# SignalEditor.net
KiCad netlist of a schematic drawn in EAGLE
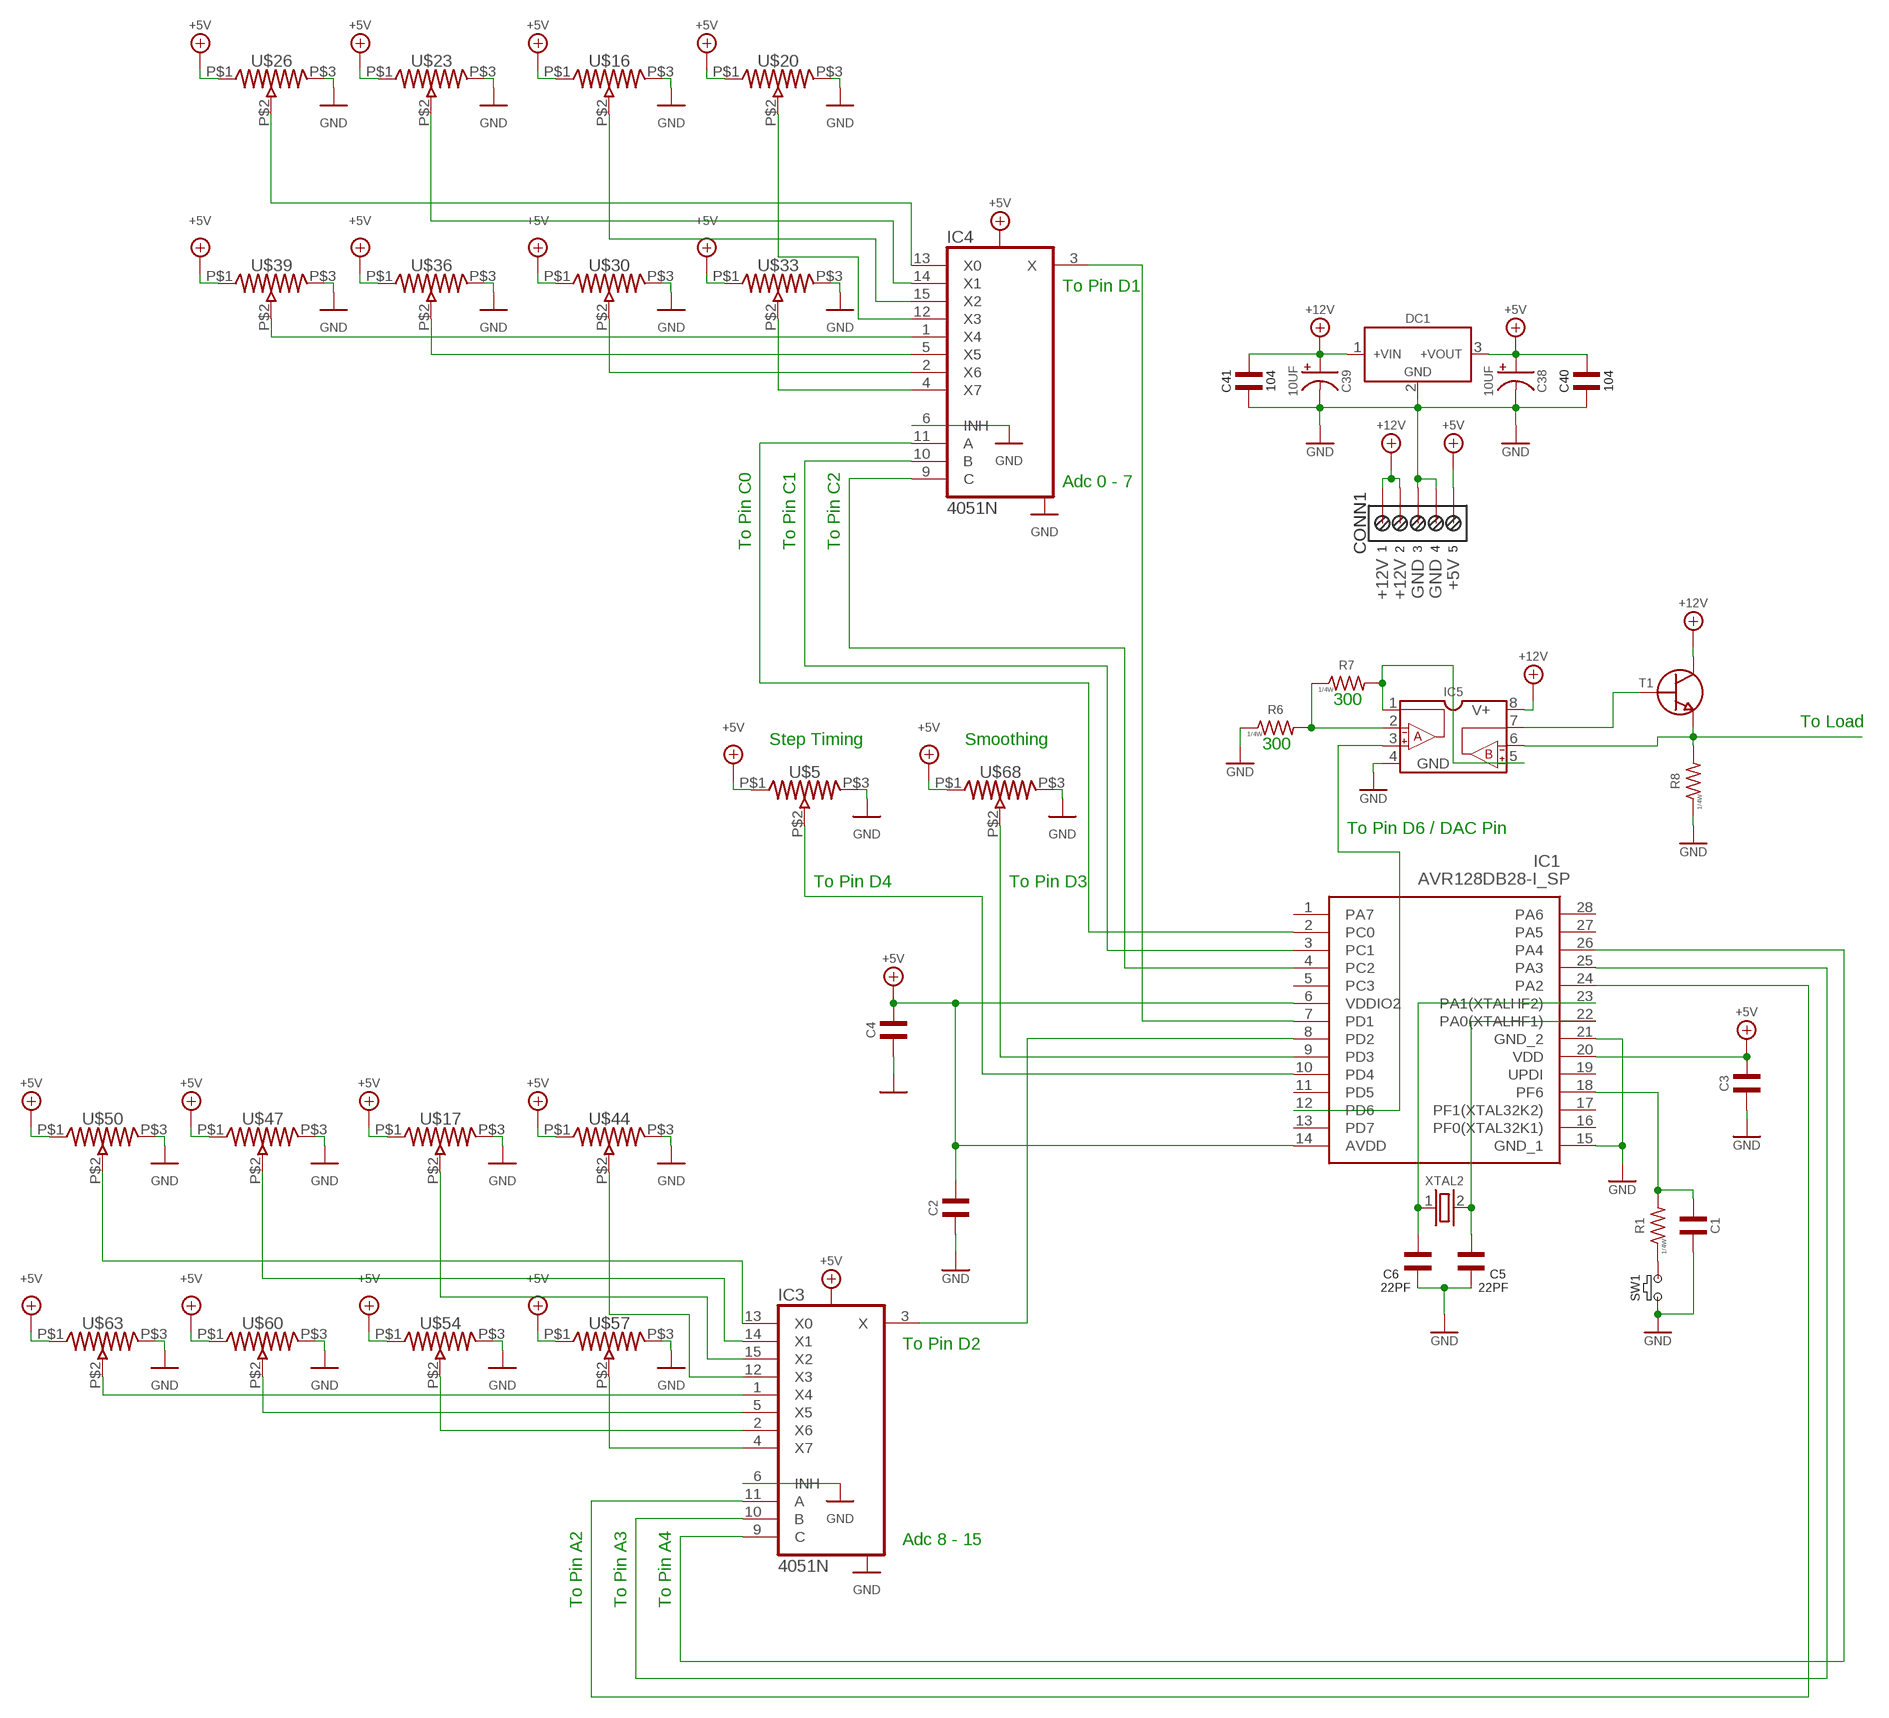
[diagram p0: schematic, sheet 1]

(export (version "E")
  (design (tool "Eeschema 10.0.6"))
  (components
    (comp (ref "C1")
      (value "040-005-032")
      (footprint "eagle-import:CAPACITOR-CERAMIC-AXIAL")
      (libsource (lib "eagle-import") (part "040-005-032"))
    )
    (comp (ref "C2")
      (value "040-005-032")
      (footprint "eagle-import:CAPACITOR-CERAMIC-AXIAL")
      (libsource (lib "eagle-import") (part "040-005-032"))
    )
    (comp (ref "C3")
      (value "040-005-032")
      (footprint "eagle-import:CAPACITOR-CERAMIC-AXIAL")
      (libsource (lib "eagle-import") (part "040-005-032"))
    )
    (comp (ref "C4")
      (value "040-005-032")
      (footprint "eagle-import:CAPACITOR-CERAMIC-AXIAL")
      (libsource (lib "eagle-import") (part "040-005-032"))
    )
    (comp (ref "C5")
      (value "22PF")
      (footprint "eagle-import:CAPACITOR-CERAMIC-AXIAL")
      (libsource (lib "eagle-import") (part "040-005-038"))
    )
    (comp (ref "C6")
      (value "22PF")
      (footprint "eagle-import:CAPACITOR-CERAMIC-AXIAL")
      (libsource (lib "eagle-import") (part "040-005-038"))
    )
    (comp (ref "C38")
      (value "10UF")
      (footprint "eagle-import:CAPACITOR-RADIAL")
      (libsource (lib "eagle-import") (part "040-005-005"))
    )
    (comp (ref "C39")
      (value "10UF")
      (footprint "eagle-import:CAPACITOR-RADIAL")
      (libsource (lib "eagle-import") (part "040-005-005"))
    )
    (comp (ref "C40")
      (value "104")
      (footprint "eagle-import:CAPACITOR-CERAMIC-AXIAL")
      (libsource (lib "eagle-import") (part "040-005-032"))
    )
    (comp (ref "C41")
      (value "104")
      (footprint "eagle-import:CAPACITOR-CERAMIC-AXIAL")
      (libsource (lib "eagle-import") (part "040-005-032"))
    )
    (comp (ref "CONN1")
      (value "030-019-017")
      (footprint "eagle-import:030-007-024")
      (libsource (lib "eagle-import") (part "030-019-017"))
    )
    (comp (ref "DC1")
      (value "5V-DC-DC-CONVERTER_RECOM")
      (footprint "eagle-import:5V-DC-DC-CONVERTER_RECOM")
      (libsource (lib "eagle-import") (part "5V-DC-DC-CONVERTER_RECOM"))
    )
    (comp (ref "IC1")
      (value "AVR128DB28-I_SP")
      (footprint "eagle-import:DIP794W56P254L3486H508Q28N")
      (fields
        (field (name "MANUFACTURER_PART_NUMBER") "AVR128DB28-I/SP")
        (field (name "MOUSER_PART_NUMBER") "579-AVR128DB28-I/SP")
      )
      (libsource (lib "eagle-import") (part "AVR128DB28-I_SP"))
    )
    (comp (ref "IC3")
      (value "4051N")
      (footprint "eagle-import:DIL16")
      (libsource (lib "eagle-import") (part "4051N"))
    )
    (comp (ref "IC4")
      (value "4051N")
      (footprint "eagle-import:DIL16")
      (libsource (lib "eagle-import") (part "4051N"))
    )
    (comp (ref "IC5")
      (value "040-002-002")
      (footprint "eagle-import:040-010-001")
      (libsource (lib "eagle-import") (part "040-002-002"))
    )
    (comp (ref "R1")
      (value "040-001-024")
      (footprint "eagle-import:RESISTOR-1_4W")
      (libsource (lib "eagle-import") (part "040-001-024"))
    )
    (comp (ref "R6")
      (value "040-001-017")
      (footprint "eagle-import:RESISTOR-1_4W")
      (libsource (lib "eagle-import") (part "040-001-017"))
    )
    (comp (ref "R7")
      (value "040-001-017")
      (footprint "eagle-import:RESISTOR-1_4W")
      (libsource (lib "eagle-import") (part "040-001-017"))
    )
    (comp (ref "R8")
      (value "040-001-015")
      (footprint "eagle-import:RESISTOR-1_4W")
      (libsource (lib "eagle-import") (part "040-001-015"))
    )
    (comp (ref "SW1")
      (value "030-011-050")
      (footprint "eagle-import:SWITCH-PB-SMD")
      (libsource (lib "eagle-import") (part "030-011-050"))
    )
    (comp (ref "T1")
      (value "040-004-002")
      (footprint "eagle-import:TRANSISTOR-TO92")
      (libsource (lib "eagle-import") (part "040-004-002"))
    )
    (comp (ref "U$5")
      (value "5K_POT_THROUGH_HOLE")
      (footprint "eagle-import:POT-TRIM-SMALL")
      (libsource (lib "eagle-import") (part "5K_POT_THROUGH_HOLE"))
    )
    (comp (ref "U$16")
      (value "5K_POT_THROUGH_HOLE")
      (footprint "eagle-import:POT-TRIM-SMALL")
      (libsource (lib "eagle-import") (part "5K_POT_THROUGH_HOLE"))
    )
    (comp (ref "U$17")
      (value "5K_POT_THROUGH_HOLE")
      (footprint "eagle-import:POT-TRIM-SMALL")
      (libsource (lib "eagle-import") (part "5K_POT_THROUGH_HOLE"))
    )
    (comp (ref "U$20")
      (value "5K_POT_THROUGH_HOLE")
      (footprint "eagle-import:POT-TRIM-SMALL")
      (libsource (lib "eagle-import") (part "5K_POT_THROUGH_HOLE"))
    )
    (comp (ref "U$23")
      (value "5K_POT_THROUGH_HOLE")
      (footprint "eagle-import:POT-TRIM-SMALL")
      (libsource (lib "eagle-import") (part "5K_POT_THROUGH_HOLE"))
    )
    (comp (ref "U$26")
      (value "5K_POT_THROUGH_HOLE")
      (footprint "eagle-import:POT-TRIM-SMALL")
      (libsource (lib "eagle-import") (part "5K_POT_THROUGH_HOLE"))
    )
    (comp (ref "U$30")
      (value "5K_POT_THROUGH_HOLE")
      (footprint "eagle-import:POT-TRIM-SMALL")
      (libsource (lib "eagle-import") (part "5K_POT_THROUGH_HOLE"))
    )
    (comp (ref "U$33")
      (value "5K_POT_THROUGH_HOLE")
      (footprint "eagle-import:POT-TRIM-SMALL")
      (libsource (lib "eagle-import") (part "5K_POT_THROUGH_HOLE"))
    )
    (comp (ref "U$36")
      (value "5K_POT_THROUGH_HOLE")
      (footprint "eagle-import:POT-TRIM-SMALL")
      (libsource (lib "eagle-import") (part "5K_POT_THROUGH_HOLE"))
    )
    (comp (ref "U$39")
      (value "5K_POT_THROUGH_HOLE")
      (footprint "eagle-import:POT-TRIM-SMALL")
      (libsource (lib "eagle-import") (part "5K_POT_THROUGH_HOLE"))
    )
    (comp (ref "U$44")
      (value "5K_POT_THROUGH_HOLE")
      (footprint "eagle-import:POT-TRIM-SMALL")
      (libsource (lib "eagle-import") (part "5K_POT_THROUGH_HOLE"))
    )
    (comp (ref "U$47")
      (value "5K_POT_THROUGH_HOLE")
      (footprint "eagle-import:POT-TRIM-SMALL")
      (libsource (lib "eagle-import") (part "5K_POT_THROUGH_HOLE"))
    )
    (comp (ref "U$50")
      (value "5K_POT_THROUGH_HOLE")
      (footprint "eagle-import:POT-TRIM-SMALL")
      (libsource (lib "eagle-import") (part "5K_POT_THROUGH_HOLE"))
    )
    (comp (ref "U$54")
      (value "5K_POT_THROUGH_HOLE")
      (footprint "eagle-import:POT-TRIM-SMALL")
      (libsource (lib "eagle-import") (part "5K_POT_THROUGH_HOLE"))
    )
    (comp (ref "U$57")
      (value "5K_POT_THROUGH_HOLE")
      (footprint "eagle-import:POT-TRIM-SMALL")
      (libsource (lib "eagle-import") (part "5K_POT_THROUGH_HOLE"))
    )
    (comp (ref "U$60")
      (value "5K_POT_THROUGH_HOLE")
      (footprint "eagle-import:POT-TRIM-SMALL")
      (libsource (lib "eagle-import") (part "5K_POT_THROUGH_HOLE"))
    )
    (comp (ref "U$63")
      (value "5K_POT_THROUGH_HOLE")
      (footprint "eagle-import:POT-TRIM-SMALL")
      (libsource (lib "eagle-import") (part "5K_POT_THROUGH_HOLE"))
    )
    (comp (ref "U$68")
      (value "5K_POT_THROUGH_HOLE")
      (footprint "eagle-import:POT-TRIM-SMALL")
      (libsource (lib "eagle-import") (part "5K_POT_THROUGH_HOLE"))
    )
    (comp (ref "XTAL2")
      (value "12MHZ-CRYSTAL-SHORT")
      (footprint "eagle-import:CRYSTAL-SHORT")
      (libsource (lib "eagle-import") (part "12MHZ-CRYSTAL-SHORT"))
    )
  )
  (nets
    (net (code "1") (name "+5V") (class "Default")
      (node (ref "C2") (pin "2") (pinfunction "2_2") (pintype "passive"))
      (node (ref "C3") (pin "2") (pinfunction "2_2") (pintype "passive"))
      (node (ref "C38") (pin "+") (pinfunction "+_+") (pintype "passive"))
      (node (ref "C4") (pin "2") (pinfunction "2_2") (pintype "passive"))
      (node (ref "C40") (pin "2") (pinfunction "2_2") (pintype "passive"))
      (node (ref "CONN1") (pin "5") (pinfunction "5_5") (pintype "passive"))
      (node (ref "DC1") (pin "3") (pinfunction "+VOUT_3") (pintype "bidirectional"))
      (node (ref "IC1") (pin "14") (pinfunction "AVDD_14") (pintype "bidirectional"))
      (node (ref "IC1") (pin "20") (pinfunction "VDD_20") (pintype "bidirectional"))
      (node (ref "IC1") (pin "6") (pinfunction "VDDIO2_6") (pintype "bidirectional"))
      (node (ref "U$16") (pin "P$1") (pinfunction "1_P$1") (pintype "passive"))
      (node (ref "U$17") (pin "P$1") (pinfunction "1_P$1") (pintype "passive"))
      (node (ref "U$20") (pin "P$1") (pinfunction "1_P$1") (pintype "passive"))
      (node (ref "U$23") (pin "P$1") (pinfunction "1_P$1") (pintype "passive"))
      (node (ref "U$26") (pin "P$1") (pinfunction "1_P$1") (pintype "passive"))
      (node (ref "U$30") (pin "P$1") (pinfunction "1_P$1") (pintype "passive"))
      (node (ref "U$33") (pin "P$1") (pinfunction "1_P$1") (pintype "passive"))
      (node (ref "U$36") (pin "P$1") (pinfunction "1_P$1") (pintype "passive"))
      (node (ref "U$39") (pin "P$1") (pinfunction "1_P$1") (pintype "passive"))
      (node (ref "U$44") (pin "P$1") (pinfunction "1_P$1") (pintype "passive"))
      (node (ref "U$47") (pin "P$1") (pinfunction "1_P$1") (pintype "passive"))
      (node (ref "U$5") (pin "P$1") (pinfunction "1_P$1") (pintype "passive"))
      (node (ref "U$50") (pin "P$1") (pinfunction "1_P$1") (pintype "passive"))
      (node (ref "U$54") (pin "P$1") (pinfunction "1_P$1") (pintype "passive"))
      (node (ref "U$57") (pin "P$1") (pinfunction "1_P$1") (pintype "passive"))
      (node (ref "U$60") (pin "P$1") (pinfunction "1_P$1") (pintype "passive"))
      (node (ref "U$63") (pin "P$1") (pinfunction "1_P$1") (pintype "passive"))
      (node (ref "U$68") (pin "P$1") (pinfunction "1_P$1") (pintype "passive"))
    )
    (net (code "2") (name "+12V") (class "Default")
      (node (ref "C39") (pin "+") (pinfunction "+_+") (pintype "passive"))
      (node (ref "C41") (pin "2") (pinfunction "2_2") (pintype "passive"))
      (node (ref "CONN1") (pin "1") (pinfunction "1_1") (pintype "passive"))
      (node (ref "CONN1") (pin "2") (pinfunction "2_2") (pintype "passive"))
      (node (ref "DC1") (pin "1") (pinfunction "+VIN_1") (pintype "bidirectional"))
      (node (ref "IC5") (pin "8") (pinfunction "V+_8") (pintype "power_in"))
      (node (ref "T1") (pin "C") (pinfunction "C_C") (pintype "passive"))
    )
    (net (code "3") (name "GND") (class "Default")
      (node (ref "C1") (pin "1") (pinfunction "1_1") (pintype "passive"))
      (node (ref "C2") (pin "1") (pinfunction "1_1") (pintype "passive"))
      (node (ref "C3") (pin "1") (pinfunction "1_1") (pintype "passive"))
      (node (ref "C38") (pin "-") (pinfunction "-_-") (pintype "passive"))
      (node (ref "C39") (pin "-") (pinfunction "-_-") (pintype "passive"))
      (node (ref "C4") (pin "1") (pinfunction "1_1") (pintype "passive"))
      (node (ref "C40") (pin "1") (pinfunction "1_1") (pintype "passive"))
      (node (ref "C41") (pin "1") (pinfunction "1_1") (pintype "passive"))
      (node (ref "C5") (pin "1") (pinfunction "1_1") (pintype "passive"))
      (node (ref "C6") (pin "1") (pinfunction "1_1") (pintype "passive"))
      (node (ref "CONN1") (pin "3") (pinfunction "3_3") (pintype "passive"))
      (node (ref "CONN1") (pin "4") (pinfunction "4_4") (pintype "passive"))
      (node (ref "DC1") (pin "2") (pinfunction "GND_2") (pintype "bidirectional"))
      (node (ref "IC1") (pin "15") (pinfunction "GND_1_15") (pintype "bidirectional"))
      (node (ref "IC1") (pin "21") (pinfunction "GND_2_21") (pintype "bidirectional"))
      (node (ref "IC3") (pin "6") (pinfunction "INH_6") (pintype "input"))
      (node (ref "IC4") (pin "6") (pinfunction "INH_6") (pintype "input"))
      (node (ref "IC5") (pin "4") (pinfunction "GND_4") (pintype "power_in"))
      (node (ref "R6") (pin "P$1") (pinfunction "1_P$1") (pintype "passive"))
      (node (ref "R8") (pin "P$1") (pinfunction "1_P$1") (pintype "passive"))
      (node (ref "SW1") (pin "1") (pinfunction "1_1") (pintype "passive"))
      (node (ref "U$16") (pin "P$3") (pinfunction "3_P$3") (pintype "passive"))
      (node (ref "U$17") (pin "P$3") (pinfunction "3_P$3") (pintype "passive"))
      (node (ref "U$20") (pin "P$3") (pinfunction "3_P$3") (pintype "passive"))
      (node (ref "U$23") (pin "P$3") (pinfunction "3_P$3") (pintype "passive"))
      (node (ref "U$26") (pin "P$3") (pinfunction "3_P$3") (pintype "passive"))
      (node (ref "U$30") (pin "P$3") (pinfunction "3_P$3") (pintype "passive"))
      (node (ref "U$33") (pin "P$3") (pinfunction "3_P$3") (pintype "passive"))
      (node (ref "U$36") (pin "P$3") (pinfunction "3_P$3") (pintype "passive"))
      (node (ref "U$39") (pin "P$3") (pinfunction "3_P$3") (pintype "passive"))
      (node (ref "U$44") (pin "P$3") (pinfunction "3_P$3") (pintype "passive"))
      (node (ref "U$47") (pin "P$3") (pinfunction "3_P$3") (pintype "passive"))
      (node (ref "U$5") (pin "P$3") (pinfunction "3_P$3") (pintype "passive"))
      (node (ref "U$50") (pin "P$3") (pinfunction "3_P$3") (pintype "passive"))
      (node (ref "U$54") (pin "P$3") (pinfunction "3_P$3") (pintype "passive"))
      (node (ref "U$57") (pin "P$3") (pinfunction "3_P$3") (pintype "passive"))
      (node (ref "U$60") (pin "P$3") (pinfunction "3_P$3") (pintype "passive"))
      (node (ref "U$63") (pin "P$3") (pinfunction "3_P$3") (pintype "passive"))
      (node (ref "U$68") (pin "P$3") (pinfunction "3_P$3") (pintype "passive"))
    )
    (net (code "4") (name "Net-(IC1-PA0(XTALHF1))") (class "Default")
      (node (ref "C5") (pin "2") (pinfunction "2_2") (pintype "passive"))
      (node (ref "IC1") (pin "22") (pinfunction "PA0(XTALHF1)_22") (pintype "bidirectional"))
      (node (ref "XTAL2") (pin "2") (pinfunction "2_2") (pintype "passive"))
    )
    (net (code "5") (name "Net-(IC1-PA1(XTALHF2))") (class "Default")
      (node (ref "C6") (pin "2") (pinfunction "2_2") (pintype "passive"))
      (node (ref "IC1") (pin "23") (pinfunction "PA1(XTALHF2)_23") (pintype "bidirectional"))
      (node (ref "XTAL2") (pin "1") (pinfunction "1_1") (pintype "passive"))
    )
    (net (code "6") (name "Net-(IC1-PA2)") (class "Default")
      (node (ref "IC1") (pin "24") (pinfunction "PA2_24") (pintype "bidirectional"))
      (node (ref "IC3") (pin "11") (pinfunction "A_11") (pintype "input"))
    )
    (net (code "7") (name "Net-(IC1-PA3)") (class "Default")
      (node (ref "IC1") (pin "25") (pinfunction "PA3_25") (pintype "bidirectional"))
      (node (ref "IC3") (pin "10") (pinfunction "B_10") (pintype "input"))
    )
    (net (code "8") (name "Net-(IC1-PA4)") (class "Default")
      (node (ref "IC1") (pin "26") (pinfunction "PA4_26") (pintype "bidirectional"))
      (node (ref "IC3") (pin "9") (pinfunction "C_9") (pintype "input"))
    )
    (net (code "9") (name "Net-(IC1-PC0)") (class "Default")
      (node (ref "IC1") (pin "2") (pinfunction "PC0_2") (pintype "bidirectional"))
      (node (ref "IC4") (pin "11") (pinfunction "A_11") (pintype "input"))
    )
    (net (code "10") (name "Net-(IC1-PC1)") (class "Default")
      (node (ref "IC1") (pin "3") (pinfunction "PC1_3") (pintype "bidirectional"))
      (node (ref "IC4") (pin "10") (pinfunction "B_10") (pintype "input"))
    )
    (net (code "11") (name "Net-(IC1-PC2)") (class "Default")
      (node (ref "IC1") (pin "4") (pinfunction "PC2_4") (pintype "bidirectional"))
      (node (ref "IC4") (pin "9") (pinfunction "C_9") (pintype "input"))
    )
    (net (code "12") (name "Net-(IC1-PD1)") (class "Default")
      (node (ref "IC1") (pin "7") (pinfunction "PD1_7") (pintype "bidirectional"))
      (node (ref "IC4") (pin "3") (pinfunction "X_3") (pintype "bidirectional"))
    )
    (net (code "13") (name "Net-(IC1-PD2)") (class "Default")
      (node (ref "IC1") (pin "8") (pinfunction "PD2_8") (pintype "bidirectional"))
      (node (ref "IC3") (pin "3") (pinfunction "X_3") (pintype "bidirectional"))
    )
    (net (code "14") (name "Net-(IC1-PD3)") (class "Default")
      (node (ref "IC1") (pin "9") (pinfunction "PD3_9") (pintype "bidirectional"))
      (node (ref "U$68") (pin "P$2") (pinfunction "2_P$2") (pintype "passive"))
    )
    (net (code "15") (name "Net-(IC1-PD4)") (class "Default")
      (node (ref "IC1") (pin "10") (pinfunction "PD4_10") (pintype "bidirectional"))
      (node (ref "U$5") (pin "P$2") (pinfunction "2_P$2") (pintype "passive"))
    )
    (net (code "16") (name "Net-(IC1-PD6)") (class "Default")
      (node (ref "IC1") (pin "12") (pinfunction "PD6_12") (pintype "bidirectional"))
      (node (ref "IC5") (pin "3") (pinfunction "+INA_3") (pintype "bidirectional"))
    )
    (net (code "17") (name "Net-(IC1-PF6)") (class "Default")
      (node (ref "C1") (pin "2") (pinfunction "2_2") (pintype "passive"))
      (node (ref "IC1") (pin "18") (pinfunction "PF6_18") (pintype "bidirectional"))
      (node (ref "R1") (pin "P$2") (pinfunction "2_P$2") (pintype "passive"))
    )
    (net (code "18") (name "Net-(IC3A-X0)") (class "Default")
      (node (ref "IC3") (pin "13") (pinfunction "X0_13") (pintype "bidirectional"))
      (node (ref "U$50") (pin "P$2") (pinfunction "2_P$2") (pintype "passive"))
    )
    (net (code "19") (name "Net-(IC3A-X1)") (class "Default")
      (node (ref "IC3") (pin "14") (pinfunction "X1_14") (pintype "bidirectional"))
      (node (ref "U$47") (pin "P$2") (pinfunction "2_P$2") (pintype "passive"))
    )
    (net (code "20") (name "Net-(IC3A-X2)") (class "Default")
      (node (ref "IC3") (pin "15") (pinfunction "X2_15") (pintype "bidirectional"))
      (node (ref "U$17") (pin "P$2") (pinfunction "2_P$2") (pintype "passive"))
    )
    (net (code "21") (name "Net-(IC3A-X3)") (class "Default")
      (node (ref "IC3") (pin "12") (pinfunction "X3_12") (pintype "bidirectional"))
      (node (ref "U$44") (pin "P$2") (pinfunction "2_P$2") (pintype "passive"))
    )
    (net (code "22") (name "Net-(IC3A-X4)") (class "Default")
      (node (ref "IC3") (pin "1") (pinfunction "X4_1") (pintype "bidirectional"))
      (node (ref "U$63") (pin "P$2") (pinfunction "2_P$2") (pintype "passive"))
    )
    (net (code "23") (name "Net-(IC3A-X5)") (class "Default")
      (node (ref "IC3") (pin "5") (pinfunction "X5_5") (pintype "bidirectional"))
      (node (ref "U$60") (pin "P$2") (pinfunction "2_P$2") (pintype "passive"))
    )
    (net (code "24") (name "Net-(IC3A-X6)") (class "Default")
      (node (ref "IC3") (pin "2") (pinfunction "X6_2") (pintype "bidirectional"))
      (node (ref "U$54") (pin "P$2") (pinfunction "2_P$2") (pintype "passive"))
    )
    (net (code "25") (name "Net-(IC3A-X7)") (class "Default")
      (node (ref "IC3") (pin "4") (pinfunction "X7_4") (pintype "bidirectional"))
      (node (ref "U$57") (pin "P$2") (pinfunction "2_P$2") (pintype "passive"))
    )
    (net (code "26") (name "Net-(IC4A-X0)") (class "Default")
      (node (ref "IC4") (pin "13") (pinfunction "X0_13") (pintype "bidirectional"))
      (node (ref "U$26") (pin "P$2") (pinfunction "2_P$2") (pintype "passive"))
    )
    (net (code "27") (name "Net-(IC4A-X1)") (class "Default")
      (node (ref "IC4") (pin "14") (pinfunction "X1_14") (pintype "bidirectional"))
      (node (ref "U$23") (pin "P$2") (pinfunction "2_P$2") (pintype "passive"))
    )
    (net (code "28") (name "Net-(IC4A-X2)") (class "Default")
      (node (ref "IC4") (pin "15") (pinfunction "X2_15") (pintype "bidirectional"))
      (node (ref "U$16") (pin "P$2") (pinfunction "2_P$2") (pintype "passive"))
    )
    (net (code "29") (name "Net-(IC4A-X3)") (class "Default")
      (node (ref "IC4") (pin "12") (pinfunction "X3_12") (pintype "bidirectional"))
      (node (ref "U$20") (pin "P$2") (pinfunction "2_P$2") (pintype "passive"))
    )
    (net (code "30") (name "Net-(IC4A-X4)") (class "Default")
      (node (ref "IC4") (pin "1") (pinfunction "X4_1") (pintype "bidirectional"))
      (node (ref "U$39") (pin "P$2") (pinfunction "2_P$2") (pintype "passive"))
    )
    (net (code "31") (name "Net-(IC4A-X5)") (class "Default")
      (node (ref "IC4") (pin "5") (pinfunction "X5_5") (pintype "bidirectional"))
      (node (ref "U$36") (pin "P$2") (pinfunction "2_P$2") (pintype "passive"))
    )
    (net (code "32") (name "Net-(IC4A-X6)") (class "Default")
      (node (ref "IC4") (pin "2") (pinfunction "X6_2") (pintype "bidirectional"))
      (node (ref "U$30") (pin "P$2") (pinfunction "2_P$2") (pintype "passive"))
    )
    (net (code "33") (name "Net-(IC4A-X7)") (class "Default")
      (node (ref "IC4") (pin "4") (pinfunction "X7_4") (pintype "bidirectional"))
      (node (ref "U$33") (pin "P$2") (pinfunction "2_P$2") (pintype "passive"))
    )
    (net (code "34") (name "Net-(IC5-+INB)") (class "Default")
      (node (ref "IC5") (pin "1") (pinfunction "OUTA_1") (pintype "bidirectional"))
      (node (ref "IC5") (pin "5") (pinfunction "+INB_5") (pintype "bidirectional"))
      (node (ref "R7") (pin "P$2") (pinfunction "2_P$2") (pintype "passive"))
    )
    (net (code "35") (name "Net-(IC5--INA)") (class "Default")
      (node (ref "IC5") (pin "2") (pinfunction "-INA_2") (pintype "bidirectional"))
      (node (ref "R6") (pin "P$2") (pinfunction "2_P$2") (pintype "passive"))
      (node (ref "R7") (pin "P$1") (pinfunction "1_P$1") (pintype "passive"))
    )
    (net (code "36") (name "Net-(IC5--INB)") (class "Default")
      (node (ref "IC5") (pin "6") (pinfunction "-INB_6") (pintype "bidirectional"))
      (node (ref "R8") (pin "P$2") (pinfunction "2_P$2") (pintype "passive"))
      (node (ref "T1") (pin "E") (pinfunction "E_E") (pintype "passive"))
    )
    (net (code "37") (name "Net-(IC5-OUTB)") (class "Default")
      (node (ref "IC5") (pin "7") (pinfunction "OUTB_7") (pintype "bidirectional"))
      (node (ref "T1") (pin "B") (pinfunction "B_B") (pintype "passive"))
    )
    (net (code "38") (name "Net-(R1-1)") (class "Default")
      (node (ref "R1") (pin "P$1") (pinfunction "1_P$1") (pintype "passive"))
      (node (ref "SW1") (pin "2") (pinfunction "2_2") (pintype "passive"))
    )
    (net (code "39") (name "unconnected-(IC1-PA5-Pad27)") (class "Default")
      (node (ref "IC1") (pin "27") (pinfunction "PA5_27") (pintype "bidirectional"))
    )
    (net (code "40") (name "unconnected-(IC1-PA6-Pad28)") (class "Default")
      (node (ref "IC1") (pin "28") (pinfunction "PA6_28") (pintype "bidirectional"))
    )
    (net (code "41") (name "unconnected-(IC1-PA7-Pad1)") (class "Default")
      (node (ref "IC1") (pin "1") (pinfunction "PA7_1") (pintype "bidirectional"))
    )
    (net (code "42") (name "unconnected-(IC1-PC3-Pad5)") (class "Default")
      (node (ref "IC1") (pin "5") (pinfunction "PC3_5") (pintype "bidirectional"))
    )
    (net (code "43") (name "unconnected-(IC1-PD5-Pad11)") (class "Default")
      (node (ref "IC1") (pin "11") (pinfunction "PD5_11") (pintype "bidirectional"))
    )
    (net (code "44") (name "unconnected-(IC1-PD7-Pad13)") (class "Default")
      (node (ref "IC1") (pin "13") (pinfunction "PD7_13") (pintype "bidirectional"))
    )
    (net (code "45") (name "unconnected-(IC1-PF0(XTAL32K1)-Pad16)") (class "Default")
      (node (ref "IC1") (pin "16") (pinfunction "PF0(XTAL32K1)_16") (pintype "bidirectional"))
    )
    (net (code "46") (name "unconnected-(IC1-PF1(XTAL32K2)-Pad17)") (class "Default")
      (node (ref "IC1") (pin "17") (pinfunction "PF1(XTAL32K2)_17") (pintype "bidirectional"))
    )
    (net (code "47") (name "unconnected-(IC1-UPDI-Pad19)") (class "Default")
      (node (ref "IC1") (pin "19") (pinfunction "UPDI_19") (pintype "bidirectional"))
    )
  )
)
